# TMP102.net
KiCad netlist of a schematic drawn in Altium Designer
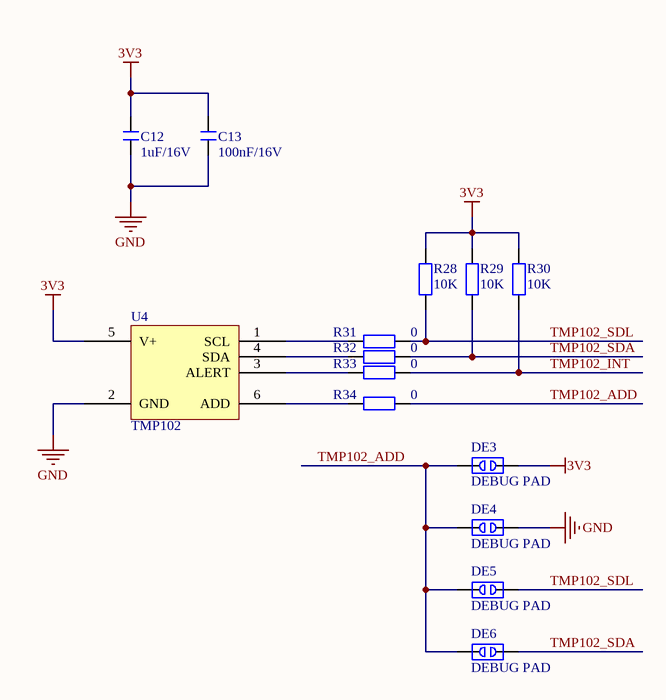
[diagram p0: TMP102.SchDoc]

(export (version "E")
  (design (tool "Eeschema 10.0.6"))
  (components
    (comp (ref "C12")
      (value "1uF/16V")
      (footprint "C 0402_L")
      (description "贴片电容")
      (libsource (lib "3.1   - 电阻-电容-电感") (part "C"))
    )
    (comp (ref "C13")
      (value "100nF/16V")
      (footprint "C 0402_L")
      (description "无极性贴片电容")
      (libsource (lib "3.1   - 电阻-电容-电感") (part "C"))
    )
    (comp (ref "DE3")
      (value "DEBUG PAD")
      (footprint "DEBUG_A")
      (description "调试断点焊盘")
      (fields (field (name "版权归属") "源创客"))
      (libsource (lib "15.1 - 未分类器件") (part "DEBUG"))
    )
    (comp (ref "DE4")
      (value "DEBUG PAD")
      (footprint "DEBUG_A")
      (description "调试断点焊盘")
      (fields (field (name "版权归属") "源创客"))
      (libsource (lib "15.1 - 未分类器件") (part "DEBUG"))
    )
    (comp (ref "DE5")
      (value "DEBUG PAD")
      (footprint "DEBUG_A")
      (description "调试断点焊盘")
      (fields (field (name "版权归属") "源创客"))
      (libsource (lib "15.1 - 未分类器件") (part "DEBUG"))
    )
    (comp (ref "DE6")
      (value "DEBUG PAD")
      (footprint "DEBUG_A")
      (description "调试断点焊盘")
      (fields (field (name "版权归属") "源创客"))
      (libsource (lib "15.1 - 未分类器件") (part "DEBUG"))
    )
    (comp (ref "R28")
      (value "10K")
      (footprint "R 0402_L")
      (description "贴片电阻 0402 1%")
      (libsource (lib "3.1   - 电阻-电容-电感") (part "R"))
    )
    (comp (ref "R29")
      (value "10K")
      (footprint "R 0402_L")
      (description "贴片电阻 0402 1%")
      (libsource (lib "3.1   - 电阻-电容-电感") (part "R"))
    )
    (comp (ref "R30")
      (value "10K")
      (footprint "R 0402_L")
      (description "贴片电阻 0402 1%")
      (libsource (lib "3.1   - 电阻-电容-电感") (part "R"))
    )
    (comp (ref "R31")
      (value "0")
      (footprint "R 0402_L")
      (description "贴片电阻")
      (libsource (lib "3.1   - 电阻-电容-电感") (part "R"))
    )
    (comp (ref "R32")
      (value "0")
      (footprint "R 0402_L")
      (description "贴片电阻")
      (libsource (lib "3.1   - 电阻-电容-电感") (part "R"))
    )
    (comp (ref "R33")
      (value "0")
      (footprint "R 0402_L")
      (description "贴片电阻")
      (libsource (lib "3.1   - 电阻-电容-电感") (part "R"))
    )
    (comp (ref "R34")
      (value "0")
      (footprint "R 0402_L")
      (description "贴片电阻")
      (libsource (lib "3.1   - 电阻-电容-电感") (part "R"))
    )
    (comp (ref "U4") (value "TMP102") (footprint "TMP102") (libsource (lib "Schlib1") (part "TMP102")))
  )
  (nets
    (net (code "1") (name "/TMP102_ADD") (class "Default")
      (node (ref "DE3") (pin "1") (pinfunction "1_1") (pintype "passive"))
      (node (ref "DE4") (pin "1") (pinfunction "1_1") (pintype "passive"))
      (node (ref "DE5") (pin "1") (pinfunction "1_1") (pintype "passive"))
      (node (ref "DE6") (pin "1") (pinfunction "1_1") (pintype "passive"))
      (node (ref "R34") (pin "1") (pinfunction "1_1") (pintype "passive"))
    )
    (net (code "2") (name "/TMP102_INT") (class "Default")
      (node (ref "R30") (pin "2") (pinfunction "2_2") (pintype "passive"))
      (node (ref "R33") (pin "1") (pinfunction "1_1") (pintype "passive"))
    )
    (net (code "3") (name "/TMP102_SDA") (class "Default")
      (node (ref "DE6") (pin "2") (pinfunction "2_2") (pintype "passive"))
      (node (ref "R29") (pin "2") (pinfunction "2_2") (pintype "passive"))
      (node (ref "R32") (pin "1") (pinfunction "1_1") (pintype "passive"))
    )
    (net (code "4") (name "/TMP102_SDL") (class "Default")
      (node (ref "DE5") (pin "2") (pinfunction "2_2") (pintype "passive"))
      (node (ref "R28") (pin "2") (pinfunction "2_2") (pintype "passive"))
      (node (ref "R31") (pin "1") (pinfunction "1_1") (pintype "passive"))
    )
    (net (code "5") (name "3V3") (class "Default")
      (node (ref "C12") (pin "2") (pinfunction "2_2") (pintype "passive"))
      (node (ref "C13") (pin "1") (pinfunction "1_1") (pintype "passive"))
      (node (ref "DE3") (pin "2") (pinfunction "2_2") (pintype "passive"))
      (node (ref "R28") (pin "1") (pinfunction "1_1") (pintype "passive"))
      (node (ref "R29") (pin "1") (pinfunction "1_1") (pintype "passive"))
      (node (ref "R30") (pin "1") (pinfunction "1_1") (pintype "passive"))
      (node (ref "U4") (pin "5") (pinfunction "V+_5") (pintype "passive"))
    )
    (net (code "6") (name "GND") (class "Default")
      (node (ref "C12") (pin "1") (pinfunction "1_1") (pintype "passive"))
      (node (ref "C13") (pin "2") (pinfunction "2_2") (pintype "passive"))
      (node (ref "DE4") (pin "2") (pinfunction "2_2") (pintype "passive"))
      (node (ref "U4") (pin "2") (pinfunction "GND_2") (pintype "passive"))
    )
    (net (code "7") (name "Net-(U4-ADD)") (class "Default")
      (node (ref "R34") (pin "2") (pinfunction "2_2") (pintype "passive"))
      (node (ref "U4") (pin "6") (pinfunction "ADD_6") (pintype "passive"))
    )
    (net (code "8") (name "Net-(U4-ALERT)") (class "Default")
      (node (ref "R33") (pin "2") (pinfunction "2_2") (pintype "passive"))
      (node (ref "U4") (pin "3") (pinfunction "ALERT_3") (pintype "passive"))
    )
    (net (code "9") (name "Net-(U4-SCL)") (class "Default")
      (node (ref "R31") (pin "2") (pinfunction "2_2") (pintype "passive"))
      (node (ref "U4") (pin "1") (pinfunction "SCL_1") (pintype "passive"))
    )
    (net (code "10") (name "Net-(U4-SDA)") (class "Default")
      (node (ref "R32") (pin "2") (pinfunction "2_2") (pintype "passive"))
      (node (ref "U4") (pin "4") (pinfunction "SDA_4") (pintype "passive"))
    )
  )
)
